# nanobox_v31.net
KiCad netlist of a schematic drawn in Altium Designer
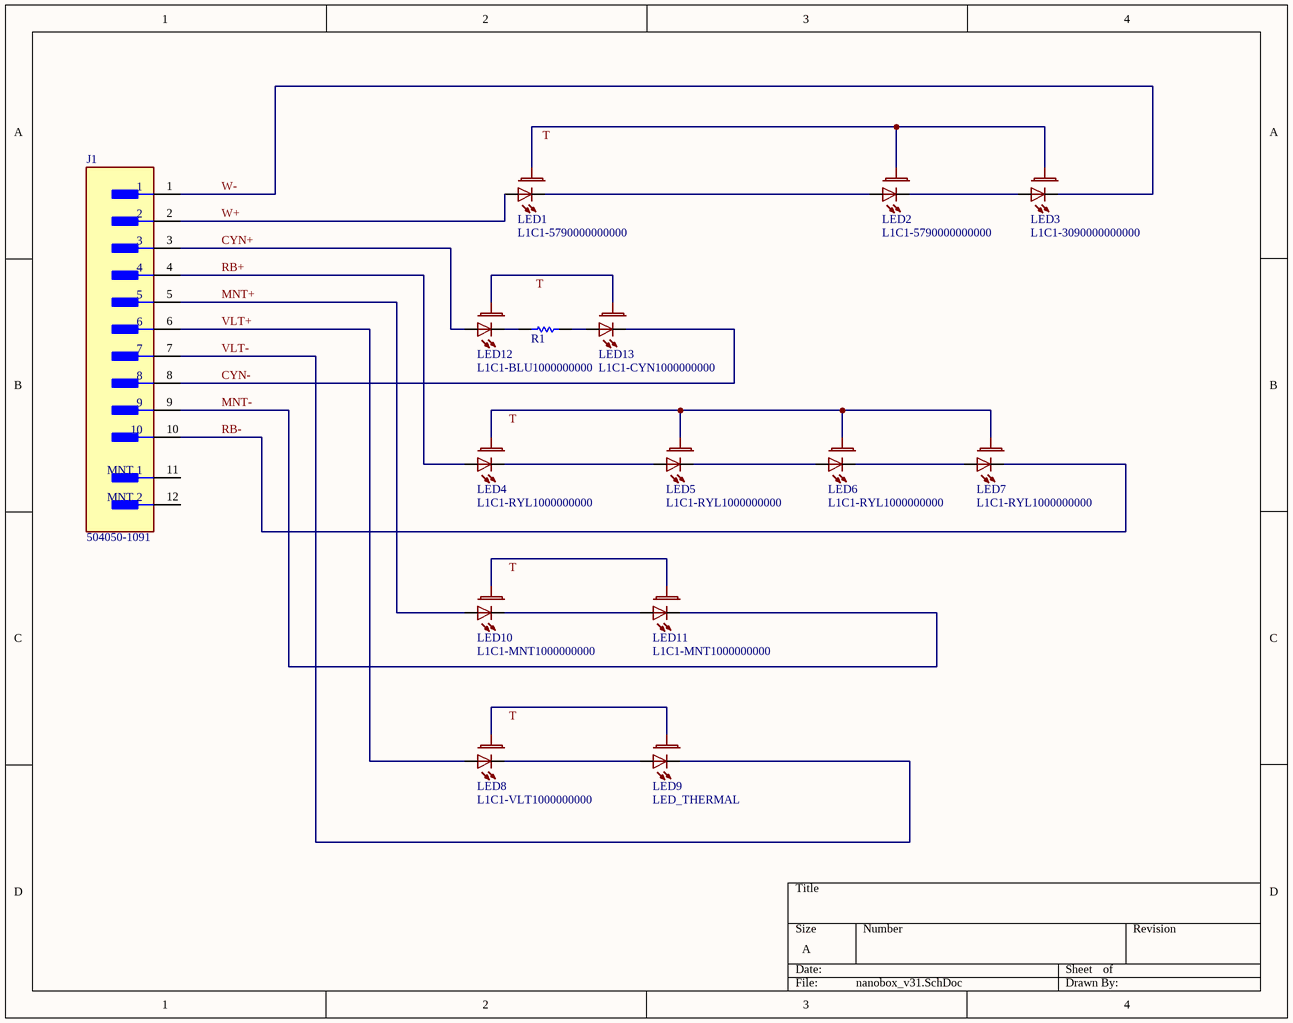
[diagram p0: nanobox_v31.SchDoc]

(export (version "E")
  (design (tool "Eeschema 10.0.6"))
  (components
    (comp (ref "J1")
      (value "504050-1091")
      (footprint "FP-504050-1091-MFG")
      (description "Conn Wire to Board HDR 10 POS 1.5mm Solder RA SMD Pico-Lock™ T/R")
      (libsource (lib "StackFoundry LLC") (part "6fa52caac0d1ee56d9e6a1d806c5b84"))
    )
    (comp (ref "LED1")
      (value "L1C1-5790000000000")
      (footprint "LUXEON_C_WIDE")
      (description "LUXEON C Color High Power LED Emitter Cool White 90 CRI 5700K 80 lm Min 350 mA")
      (libsource (lib "StackFoundry LLC") (part "LED_THERMAL"))
    )
    (comp (ref "LED2")
      (value "L1C1-5790000000000")
      (footprint "LUXEON_C_WIDE")
      (description "LUXEON C Color High Power LED Emitter Cool White 90 CRI 5700K 80 lm Min 350 mA")
      (libsource (lib "StackFoundry LLC") (part "LED_THERMAL"))
    )
    (comp (ref "LED3")
      (value "L1C1-3090000000000")
      (footprint "LUXEON_C_WIDE")
      (description "LED Chip Warm White 3000K 1225mA 2-Pin SMD T/R")
      (libsource (lib "StackFoundry LLC") (part "LED_THERMAL"))
    )
    (comp (ref "LED4")
      (value "L1C1-RYL1000000000")
      (footprint "LUXEON_C_WIDE")
      (description "High Power LEDs - Single Color Royal Blue")
      (libsource (lib "StackFoundry LLC") (part "LED_THERMAL"))
    )
    (comp (ref "LED5")
      (value "L1C1-RYL1000000000")
      (footprint "LUXEON_C_WIDE")
      (description "High Power LEDs - Single Color Royal Blue")
      (libsource (lib "StackFoundry LLC") (part "LED_THERMAL"))
    )
    (comp (ref "LED6")
      (value "L1C1-RYL1000000000")
      (footprint "LUXEON_C_WIDE")
      (description "High Power LEDs - Single Color Royal Blue")
      (libsource (lib "StackFoundry LLC") (part "LED_THERMAL"))
    )
    (comp (ref "LED7")
      (value "L1C1-RYL1000000000")
      (footprint "LUXEON_C_WIDE")
      (description "High Power LEDs - Single Color Royal Blue")
      (libsource (lib "StackFoundry LLC") (part "LED_THERMAL"))
    )
    (comp (ref "LED8")
      (value "L1C1-VLT1000000000")
      (footprint "LUXEON_C_WIDE")
      (description "LED Uni-Color Violet 430nm 2-Pin SMD EP T/R")
      (libsource (lib "StackFoundry LLC") (part "LED_THERMAL"))
    )
    (comp (ref "LED9")
      (value "LED_THERMAL")
      (footprint "VIOSYS_Z5")
      (libsource (lib "StackFoundry LLC") (part "LED_THERMAL"))
    )
    (comp (ref "LED10")
      (value "L1C1-MNT1000000000")
      (footprint "LUXEON_C_WIDE")
      (description "LUXEON C High Power Surface Mount LED Emitter Mint 350 mA 2.75 V")
      (libsource (lib "StackFoundry LLC") (part "LED_THERMAL"))
    )
    (comp (ref "LED11")
      (value "L1C1-MNT1000000000")
      (footprint "LUXEON_C_WIDE")
      (description "LUXEON C High Power Surface Mount LED Emitter Mint 350 mA 2.75 V")
      (libsource (lib "StackFoundry LLC") (part "LED_THERMAL"))
    )
    (comp (ref "LED12")
      (value "L1C1-BLU1000000000")
      (footprint "LUXEON_C_WIDE")
      (description "LED LUXEON BLUE 470NM L1")
      (libsource (lib "StackFoundry LLC") (part "LED_THERMAL"))
    )
    (comp (ref "LED13")
      (value "L1C1-CYN1000000000")
      (footprint "LUXEON_C_WIDE")
      (description "LUXEON C High Power Surface Mount LED Emitter Cyan 350 mA 2.6 V")
      (libsource (lib "StackFoundry LLC") (part "LED_THERMAL"))
    )
    (comp (ref "R1")
      (value "0R 2512 1W")
      (footprint "RESC2512(6432)_M")
      (description "Res Thick Film 2512 0 Ohm Molded SMD Automotive Blister T/R")
      (libsource (lib "StackFoundry LLC") (part "RES"))
    )
  )
  (nets
    (net (code "1") (name "/CYN+") (class "Default")
      (node (ref "J1") (pin "3") (pinfunction "3_3") (pintype "passive"))
      (node (ref "LED12") (pin "A") (pinfunction "A_A") (pintype "passive"))
    )
    (net (code "2") (name "/CYN-") (class "Default")
      (node (ref "J1") (pin "8") (pinfunction "8_8") (pintype "passive"))
      (node (ref "LED13") (pin "C") (pinfunction "C_C") (pintype "passive"))
    )
    (net (code "3") (name "/MNT+") (class "Default")
      (node (ref "J1") (pin "5") (pinfunction "5_5") (pintype "passive"))
      (node (ref "LED10") (pin "A") (pinfunction "A_A") (pintype "passive"))
    )
    (net (code "4") (name "/MNT-") (class "Default")
      (node (ref "J1") (pin "9") (pinfunction "9_9") (pintype "passive"))
      (node (ref "LED11") (pin "C") (pinfunction "C_C") (pintype "passive"))
    )
    (net (code "5") (name "/RB+") (class "Default")
      (node (ref "J1") (pin "4") (pinfunction "4_4") (pintype "passive"))
      (node (ref "LED4") (pin "A") (pinfunction "A_A") (pintype "passive"))
    )
    (net (code "6") (name "/RB-") (class "Default")
      (node (ref "J1") (pin "10") (pinfunction "10_10") (pintype "passive"))
      (node (ref "LED7") (pin "C") (pinfunction "C_C") (pintype "passive"))
    )
    (net (code "7") (name "/T") (class "Default")
      (node (ref "LED1") (pin "PAD") (pinfunction "PAD_PAD") (pintype "passive"))
      (node (ref "LED10") (pin "PAD") (pinfunction "PAD_PAD") (pintype "passive"))
      (node (ref "LED11") (pin "PAD") (pinfunction "PAD_PAD") (pintype "passive"))
      (node (ref "LED12") (pin "PAD") (pinfunction "PAD_PAD") (pintype "passive"))
      (node (ref "LED13") (pin "PAD") (pinfunction "PAD_PAD") (pintype "passive"))
      (node (ref "LED2") (pin "PAD") (pinfunction "PAD_PAD") (pintype "passive"))
      (node (ref "LED3") (pin "PAD") (pinfunction "PAD_PAD") (pintype "passive"))
      (node (ref "LED4") (pin "PAD") (pinfunction "PAD_PAD") (pintype "passive"))
      (node (ref "LED5") (pin "PAD") (pinfunction "PAD_PAD") (pintype "passive"))
      (node (ref "LED6") (pin "PAD") (pinfunction "PAD_PAD") (pintype "passive"))
      (node (ref "LED7") (pin "PAD") (pinfunction "PAD_PAD") (pintype "passive"))
      (node (ref "LED8") (pin "PAD") (pinfunction "PAD_PAD") (pintype "passive"))
      (node (ref "LED9") (pin "PAD") (pinfunction "PAD_PAD") (pintype "passive"))
    )
    (net (code "8") (name "/VLT+") (class "Default")
      (node (ref "J1") (pin "6") (pinfunction "6_6") (pintype "passive"))
      (node (ref "LED8") (pin "A") (pinfunction "A_A") (pintype "passive"))
    )
    (net (code "9") (name "/VLT-") (class "Default")
      (node (ref "J1") (pin "7") (pinfunction "7_7") (pintype "passive"))
      (node (ref "LED9") (pin "C") (pinfunction "C_C") (pintype "passive"))
    )
    (net (code "10") (name "/W+") (class "Default")
      (node (ref "J1") (pin "2") (pinfunction "2_2") (pintype "passive"))
      (node (ref "LED1") (pin "A") (pinfunction "A_A") (pintype "passive"))
    )
    (net (code "11") (name "/W-") (class "Default")
      (node (ref "J1") (pin "1") (pinfunction "1_1") (pintype "passive"))
      (node (ref "LED3") (pin "C") (pinfunction "C_C") (pintype "passive"))
    )
    (net (code "12") (name "Net-(LED1-PadC)") (class "Default")
      (node (ref "LED1") (pin "C") (pinfunction "C_C") (pintype "passive"))
      (node (ref "LED2") (pin "A") (pinfunction "A_A") (pintype "passive"))
    )
    (net (code "13") (name "Net-(LED2-PadC)") (class "Default")
      (node (ref "LED2") (pin "C") (pinfunction "C_C") (pintype "passive"))
      (node (ref "LED3") (pin "A") (pinfunction "A_A") (pintype "passive"))
    )
    (net (code "14") (name "Net-(LED4-PadC)") (class "Default")
      (node (ref "LED4") (pin "C") (pinfunction "C_C") (pintype "passive"))
      (node (ref "LED5") (pin "A") (pinfunction "A_A") (pintype "passive"))
    )
    (net (code "15") (name "Net-(LED5-PadC)") (class "Default")
      (node (ref "LED5") (pin "C") (pinfunction "C_C") (pintype "passive"))
      (node (ref "LED6") (pin "A") (pinfunction "A_A") (pintype "passive"))
    )
    (net (code "16") (name "Net-(LED6-PadC)") (class "Default")
      (node (ref "LED6") (pin "C") (pinfunction "C_C") (pintype "passive"))
      (node (ref "LED7") (pin "A") (pinfunction "A_A") (pintype "passive"))
    )
    (net (code "17") (name "Net-(LED8-PadC)") (class "Default")
      (node (ref "LED8") (pin "C") (pinfunction "C_C") (pintype "passive"))
      (node (ref "LED9") (pin "A") (pinfunction "A_A") (pintype "passive"))
    )
    (net (code "18") (name "Net-(LED10-PadC)") (class "Default")
      (node (ref "LED10") (pin "C") (pinfunction "C_C") (pintype "passive"))
      (node (ref "LED11") (pin "A") (pinfunction "A_A") (pintype "passive"))
    )
    (net (code "19") (name "Net-(LED12-PadC)") (class "Default")
      (node (ref "LED12") (pin "C") (pinfunction "C_C") (pintype "passive"))
      (node (ref "R1") (pin "2") (pinfunction "2_2") (pintype "passive"))
    )
    (net (code "20") (name "Net-(LED13-PadA)") (class "Default")
      (node (ref "LED13") (pin "A") (pinfunction "A_A") (pintype "passive"))
      (node (ref "R1") (pin "1") (pinfunction "1_1") (pintype "passive"))
    )
    (net (code "21") (name "unconnected-(J1-MNT_1-Pad11)") (class "Default")
      (node (ref "J1") (pin "11") (pinfunction "MNT_1_11") (pintype "passive"))
    )
    (net (code "22") (name "unconnected-(J1-MNT_2-Pad12)") (class "Default")
      (node (ref "J1") (pin "12") (pinfunction "MNT_2_12") (pintype "passive"))
    )
  )
)
